# Cpt_Temp.net
KiCad netlist of a schematic drawn in Altium Designer
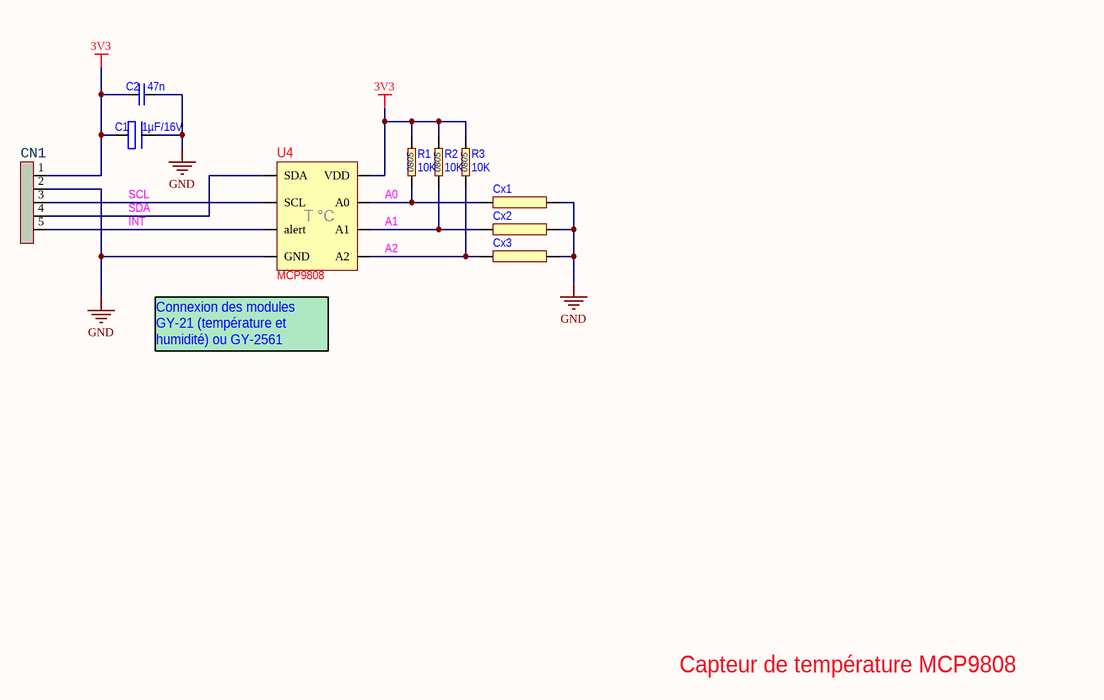
[diagram p0: Cpt_Temp.SchDoc]

(export (version "E")
  (design (tool "Eeschema 10.0.6"))
  (components
    (comp (ref "C1")
      (value "1µF/16V")
      (footprint "3216-18")
      (description "145-7406 case 3216-18")
      (libsource (lib "CMS") (part "tantale 1µF/16V"))
    )
    (comp (ref "C2")
      (value "47n")
      (footprint "0805")
      (description "CMS 0805")
      (libsource (lib "CMS") (part "Cap_CMS_0805"))
    )
    (comp (ref "CN1")
      (value "inch_ligne 1x5")
      (footprint "INCH_1x5_droit")
      (description "Inch_1x5_droit")
      (libsource (lib "Connecteurs Contacts") (part "Inch_1x5_droit"))
    )
    (comp (ref "Cx1")
      (value "Pont")
      (footprint "0402")
      (description "Pont pour configuration I2C")
      (libsource (lib "CMS") (part "Pont"))
    )
    (comp (ref "Cx2")
      (value "Pont")
      (footprint "0402")
      (description "Pont pour configuration I2C")
      (libsource (lib "CMS") (part "Pont"))
    )
    (comp (ref "Cx3")
      (value "Pont")
      (footprint "0402")
      (description "Pont pour configuration I2C")
      (libsource (lib "CMS") (part "Pont"))
    )
    (comp (ref "R1")
      (value "10K")
      (footprint "0805")
      (description "CMS 0805")
      (libsource (lib "CMS") (part "Res CMS 0805"))
    )
    (comp (ref "R2")
      (value "10K")
      (footprint "0805")
      (description "CMS 0805")
      (libsource (lib "CMS") (part "Res CMS 0805"))
    )
    (comp (ref "R3")
      (value "10K")
      (footprint "0805")
      (description "CMS 0805")
      (libsource (lib "CMS") (part "Res CMS 0805"))
    )
    (comp (ref "U4")
      (value "MCP9808")
      (footprint "MSOP-08")
      (description "Digital temperature Sensor")
      (libsource (lib "CMS") (part "MCP9808"))
    )
  )
  (nets
    (net (code "1") (name "/A0") (class "Default")
      (node (ref "Cx1") (pin "1") (pinfunction "P1_1") (pintype "passive"))
      (node (ref "R1") (pin "1") (pinfunction "CT1_1") (pintype "passive"))
      (node (ref "U4") (pin "7") (pinfunction "A0_7") (pintype "passive"))
    )
    (net (code "2") (name "/A1") (class "Default")
      (node (ref "Cx2") (pin "1") (pinfunction "P1_1") (pintype "passive"))
      (node (ref "R2") (pin "1") (pinfunction "CT1_1") (pintype "passive"))
      (node (ref "U4") (pin "6") (pinfunction "A1_6") (pintype "passive"))
    )
    (net (code "3") (name "/A2") (class "Default")
      (node (ref "Cx3") (pin "1") (pinfunction "P1_1") (pintype "passive"))
      (node (ref "R3") (pin "1") (pinfunction "CT1_1") (pintype "passive"))
      (node (ref "U4") (pin "5") (pinfunction "A2_5") (pintype "passive"))
    )
    (net (code "4") (name "/INT") (class "Default")
      (node (ref "CN1") (pin "5") (pintype "passive"))
      (node (ref "U4") (pin "3") (pinfunction "alert_3") (pintype "passive"))
    )
    (net (code "5") (name "/SCL") (class "Default")
      (node (ref "CN1") (pin "3") (pintype "passive"))
      (node (ref "U4") (pin "2") (pinfunction "SCL_2") (pintype "passive"))
    )
    (net (code "6") (name "/SDA") (class "Default")
      (node (ref "CN1") (pin "4") (pintype "passive"))
      (node (ref "U4") (pin "1") (pinfunction "SDA_1") (pintype "passive"))
    )
    (net (code "7") (name "3V3") (class "Default")
      (node (ref "C1") (pin "1") (pinfunction "V+_1") (pintype "passive"))
      (node (ref "C2") (pin "1") (pinfunction "CT1_1") (pintype "passive"))
      (node (ref "CN1") (pin "1") (pintype "passive"))
      (node (ref "R1") (pin "2") (pinfunction "CT2_2") (pintype "passive"))
      (node (ref "R2") (pin "2") (pinfunction "CT2_2") (pintype "passive"))
      (node (ref "R3") (pin "2") (pinfunction "CT2_2") (pintype "passive"))
      (node (ref "U4") (pin "8") (pinfunction "VDD_8") (pintype "passive"))
    )
    (net (code "8") (name "GND") (class "Default")
      (node (ref "C1") (pin "2") (pinfunction "V-_2") (pintype "passive"))
      (node (ref "C2") (pin "2") (pinfunction "CT2_2") (pintype "passive"))
      (node (ref "CN1") (pin "2") (pintype "passive"))
      (node (ref "Cx1") (pin "2") (pinfunction "P2_2") (pintype "passive"))
      (node (ref "Cx2") (pin "2") (pinfunction "P2_2") (pintype "passive"))
      (node (ref "Cx3") (pin "2") (pinfunction "P2_2") (pintype "passive"))
      (node (ref "U4") (pin "4") (pinfunction "GND_4") (pintype "passive"))
    )
  )
)
